# mc_ds.net
KiCad netlist of a schematic drawn in Altium Designer
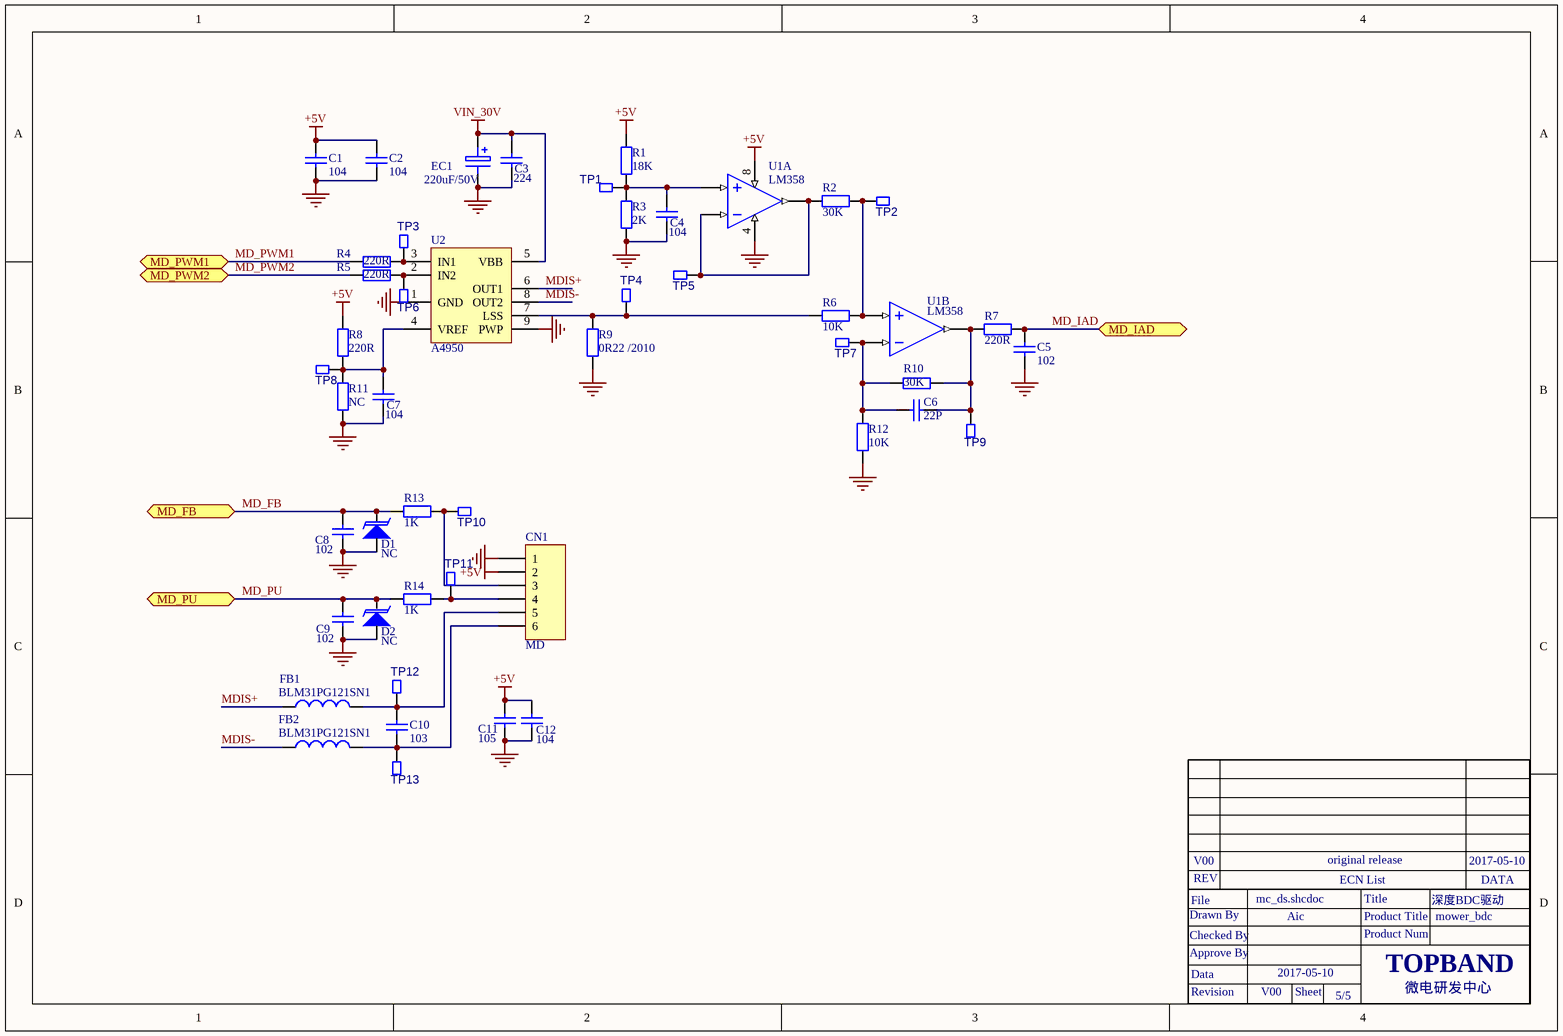
[diagram p0: mc_ds.SchDoc]

(export (version "E")
  (design (tool "Eeschema 10.0.6"))
  (components
    (comp (ref "C1")
      (value "104")
      (footprint "0603C")
      (libsource (lib "altium-import") (part "root_3_mirrored_Cap(0603)_"))
    )
    (comp (ref "C2")
      (value "104")
      (footprint "0603C")
      (libsource (lib "altium-import") (part "root_3_mirrored_Cap(0603)_"))
    )
    (comp (ref "C3")
      (value "224")
      (footprint "0805C")
      (libsource (lib "altium-import") (part "root_3_mirrored_Cap(0603)_"))
    )
    (comp (ref "C4")
      (value "104")
      (footprint "0603C")
      (libsource (lib "altium-import") (part "root_3_mirrored_Cap(0603)_"))
    )
    (comp (ref "C5")
      (value "102")
      (footprint "0603C")
      (libsource (lib "altium-import") (part "root_1_mirrored_Cap(0603)_"))
    )
    (comp (ref "C6")
      (value "22P")
      (footprint "0603C")
      (libsource (lib "altium-import") (part "root_0_mirrored_Cap(0603)_"))
    )
    (comp (ref "C7")
      (value "104")
      (footprint "0603C")
      (libsource (lib "altium-import") (part "root_3_mirrored_Cap(0603)_"))
    )
    (comp (ref "C8")
      (value "102")
      (footprint "0603C")
      (libsource (lib "altium-import") (part "root_1_mirrored_Cap(0603)_"))
    )
    (comp (ref "C9")
      (value "102")
      (footprint "0603C")
      (libsource (lib "altium-import") (part "root_1_mirrored_Cap(0603)_"))
    )
    (comp (ref "C10")
      (value "103")
      (footprint "0805C")
      (libsource (lib "altium-import") (part "root_1_mirrored_Cap(0603)_"))
    )
    (comp (ref "C11")
      (value "105")
      (footprint "0805C")
      (libsource (lib "altium-import") (part "root_1_mirrored_Cap(0603)_"))
    )
    (comp (ref "C12")
      (value "104")
      (footprint "0603C")
      (libsource (lib "altium-import") (part "root_1_mirrored_Cap(0603)_"))
    )
    (comp (ref "CN1")
      (value "MD")
      (footprint "CON6-2.54")
      (description "Header, 6-Pin")
      (fields (field (name "PUBLISHER") "Altium Limited"))
      (libsource (lib "Miscellaneous Connectors") (part "Header 6"))
    )
    (comp (ref "D1")
      (value "NC")
      (footprint "SOD-123")
      (description "TVS管")
      (fields (field (name "PART NUMBER") "Diode(TVS_贴片)_1"))
      (libsource (lib "分立器件1") (part "Diode(TVS_贴片)_1"))
    )
    (comp (ref "D2")
      (value "NC")
      (footprint "SOD-123")
      (description "TVS管")
      (fields (field (name "PART NUMBER") "Diode(TVS_贴片)_1"))
      (libsource (lib "分立器件1") (part "Diode(TVS_贴片)_1"))
    )
    (comp (ref "EC1")
      (value "220uF/50V")
      (footprint "EC10")
      (description "电解电容")
      (fields (field (name "PART NUMBER") "Electro(2.5mm)"))
      (libsource (lib "分立器件1") (part "Electro(2.5mm)"))
    )
    (comp (ref "FB1")
      (value "BLM31PG121SN1")
      (footprint "1206R")
      (description "电感")
      (fields (field (name "PART NUMBER") "Inductor"))
      (libsource (lib "分立器件1") (part "Inductor"))
    )
    (comp (ref "FB2")
      (value "BLM31PG121SN1")
      (footprint "1206R")
      (description "电感")
      (fields (field (name "PART NUMBER") "Inductor"))
      (libsource (lib "分立器件1") (part "Inductor"))
    )
    (comp (ref "R1")
      (value "18K")
      (footprint "0603R")
      (description "Resistor")
      (fields (field (name "PUBLISHER") "Altium Limited"))
      (libsource (lib "") (part "Res2_2"))
    )
    (comp (ref "R2")
      (value "30K")
      (footprint "0603R")
      (description "Resistor")
      (fields (field (name "PUBLISHER") "Altium Limited"))
      (libsource (lib "Miscellaneous Devices") (part "Res2"))
    )
    (comp (ref "R3")
      (value "2K")
      (footprint "0603R")
      (description "Resistor")
      (fields (field (name "PUBLISHER") "Altium Limited"))
      (libsource (lib "") (part "Res2_2"))
    )
    (comp (ref "R4")
      (value "220R")
      (footprint "0603R")
      (description "Resistor")
      (fields (field (name "PUBLISHER") "Altium Limited"))
      (libsource (lib "Miscellaneous Devices") (part "Res2"))
    )
    (comp (ref "R5")
      (value "220R")
      (footprint "0603R")
      (description "Resistor")
      (fields (field (name "PUBLISHER") "Altium Limited"))
      (libsource (lib "Miscellaneous Devices") (part "Res2"))
    )
    (comp (ref "R6")
      (value "10K")
      (footprint "0603R")
      (description "Resistor")
      (fields (field (name "PUBLISHER") "Altium Limited"))
      (libsource (lib "Miscellaneous Devices") (part "Res2"))
    )
    (comp (ref "R7")
      (value "220R")
      (footprint "0603R")
      (description "Resistor")
      (fields (field (name "PUBLISHER") "Altium Limited"))
      (libsource (lib "Miscellaneous Devices") (part "Res2"))
    )
    (comp (ref "R8")
      (value "220R")
      (footprint "0603R")
      (description "Resistor")
      (fields (field (name "PUBLISHER") "Altium Limited"))
      (libsource (lib "") (part "Res2_1"))
    )
    (comp (ref "R9")
      (value "0R22 /2010")
      (footprint "2010R")
      (description "Resistor")
      (fields (field (name "PUBLISHER") "Altium Limited"))
      (libsource (lib "") (part "Res2_1"))
    )
    (comp (ref "R10")
      (value "30K")
      (footprint "0603R")
      (description "Resistor")
      (fields (field (name "PUBLISHER") "Altium Limited"))
      (libsource (lib "") (part "Res2_3"))
    )
    (comp (ref "R11")
      (value "NC")
      (footprint "0603R")
      (description "Resistor")
      (fields (field (name "PUBLISHER") "Altium Limited"))
      (libsource (lib "") (part "Res2_2"))
    )
    (comp (ref "R12")
      (value "10K")
      (footprint "0603R")
      (description "Resistor")
      (fields (field (name "PUBLISHER") "Altium Limited"))
      (libsource (lib "") (part "Res2_2"))
    )
    (comp (ref "R13")
      (value "1K")
      (footprint "0603R")
      (description "Resistor")
      (fields (field (name "PUBLISHER") "Altium Limited"))
      (libsource (lib "") (part "Res2_3"))
    )
    (comp (ref "R14")
      (value "1K")
      (footprint "0603R")
      (description "Resistor")
      (fields (field (name "PUBLISHER") "Altium Limited"))
      (libsource (lib "") (part "Res2_3"))
    )
    (comp (ref "TP1") (value "TP") (footprint "TEST-0.8MM") (libsource (lib "Topband1") (part "TP")))
    (comp (ref "TP2") (value "TP") (footprint "TEST-0.8MM") (libsource (lib "Topband1") (part "TP")))
    (comp (ref "TP3") (value "TP") (footprint "TEST-0.8MM") (libsource (lib "Topband1") (part "TP")))
    (comp (ref "TP4") (value "TP") (footprint "TEST-0.8MM") (libsource (lib "Topband1") (part "TP")))
    (comp (ref "TP5") (value "TP") (footprint "TEST-0.8MM") (libsource (lib "Topband1") (part "TP")))
    (comp (ref "TP6") (value "TP") (footprint "TEST-0.8MM") (libsource (lib "Topband1") (part "TP")))
    (comp (ref "TP7") (value "TP") (footprint "TEST-0.8MM") (libsource (lib "Topband1") (part "TP")))
    (comp (ref "TP8") (value "TP") (footprint "TEST-0.8MM") (libsource (lib "Topband1") (part "TP")))
    (comp (ref "TP9") (value "TP") (footprint "TEST-0.8MM") (libsource (lib "Topband1") (part "TP")))
    (comp (ref "TP10") (value "TP") (footprint "TEST-0.8MM") (libsource (lib "Topband1") (part "TP")))
    (comp (ref "TP11") (value "TP") (footprint "TEST-0.8MM") (libsource (lib "Topband1") (part "TP")))
    (comp (ref "TP12") (value "TP") (footprint "TEST-0.8MM") (libsource (lib "Topband1") (part "TP")))
    (comp (ref "TP13") (value "TP") (footprint "TEST-0.8MM") (libsource (lib "Topband1") (part "TP")))
    (comp (ref "U1")
      (value "LM358")
      (footprint "SO-8")
      (description "集成电路")
      (fields (field (name "PART NUMBER") "IC_LM358"))
      (libsource (lib "接插器件+IC") (part "IC_LM358"))
    )
    (comp (ref "U2") (value "A4950") (footprint "SO-8 - E") (libsource (lib "Schlib") (part "A4950")))
  )
  (nets
    (net (code "1") (name "+5V") (class "Default")
      (node (ref "C1") (pin "2") (pinfunction "2_2") (pintype "passive"))
      (node (ref "C11") (pin "1") (pinfunction "1_1") (pintype "passive"))
      (node (ref "C12") (pin "1") (pinfunction "1_1") (pintype "passive"))
      (node (ref "C2") (pin "2") (pinfunction "2_2") (pintype "passive"))
      (node (ref "CN1") (pin "2") (pinfunction "2_2") (pintype "passive"))
      (node (ref "R1") (pin "2") (pinfunction "2_2") (pintype "passive"))
      (node (ref "R8") (pin "1") (pinfunction "1_1") (pintype "passive"))
      (node (ref "U1") (pin "8") (pinfunction "VCC_8") (pintype "input"))
    )
    (net (code "2") (name "/MDIS+") (class "Default")
      (node (ref "FB1") (pin "1") (pinfunction "1_1") (pintype "passive"))
      (node (ref "U2") (pin "6") (pinfunction "OUT1_6") (pintype "passive"))
    )
    (net (code "3") (name "/MDIS-") (class "Default")
      (node (ref "FB2") (pin "1") (pinfunction "1_1") (pintype "passive"))
      (node (ref "U2") (pin "8") (pinfunction "OUT2_8") (pintype "passive"))
    )
    (net (code "4") (name "/MD_FB") (class "Default")
      (node (ref "C8") (pin "1") (pinfunction "1_1") (pintype "passive"))
      (node (ref "D1") (pin "K") (pinfunction "K_K") (pintype "passive"))
      (node (ref "R13") (pin "2") (pinfunction "2_2") (pintype "passive"))
    )
    (net (code "5") (name "/MD_IAD") (class "Default")
      (node (ref "C5") (pin "1") (pinfunction "1_1") (pintype "passive"))
      (node (ref "R7") (pin "2") (pinfunction "2_2") (pintype "passive"))
    )
    (net (code "6") (name "/MD_PU") (class "Default")
      (node (ref "C9") (pin "1") (pinfunction "1_1") (pintype "passive"))
      (node (ref "D2") (pin "K") (pinfunction "K_K") (pintype "passive"))
      (node (ref "R14") (pin "2") (pinfunction "2_2") (pintype "passive"))
    )
    (net (code "7") (name "/MD_PWM1") (class "Default")
      (node (ref "R4") (pin "1") (pinfunction "1_1") (pintype "passive"))
    )
    (net (code "8") (name "/MD_PWM2") (class "Default")
      (node (ref "R5") (pin "1") (pinfunction "1_1") (pintype "passive"))
    )
    (net (code "9") (name "GND") (class "Default")
      (node (ref "C1") (pin "1") (pinfunction "1_1") (pintype "passive"))
      (node (ref "C11") (pin "2") (pinfunction "2_2") (pintype "passive"))
      (node (ref "C12") (pin "2") (pinfunction "2_2") (pintype "passive"))
      (node (ref "C2") (pin "1") (pinfunction "1_1") (pintype "passive"))
      (node (ref "C3") (pin "1") (pinfunction "1_1") (pintype "passive"))
      (node (ref "C4") (pin "1") (pinfunction "1_1") (pintype "passive"))
      (node (ref "C5") (pin "2") (pinfunction "2_2") (pintype "passive"))
      (node (ref "C7") (pin "1") (pinfunction "1_1") (pintype "passive"))
      (node (ref "C8") (pin "2") (pinfunction "2_2") (pintype "passive"))
      (node (ref "C9") (pin "2") (pinfunction "2_2") (pintype "passive"))
      (node (ref "CN1") (pin "1") (pinfunction "1_1") (pintype "passive"))
      (node (ref "D1") (pin "A") (pinfunction "A_A") (pintype "passive"))
      (node (ref "D2") (pin "A") (pinfunction "A_A") (pintype "passive"))
      (node (ref "EC1") (pin "2") (pinfunction "2_2") (pintype "passive"))
      (node (ref "R11") (pin "1") (pinfunction "1_1") (pintype "passive"))
      (node (ref "R12") (pin "1") (pinfunction "1_1") (pintype "passive"))
      (node (ref "R3") (pin "1") (pinfunction "1_1") (pintype "passive"))
      (node (ref "R9") (pin "2") (pinfunction "2_2") (pintype "passive"))
      (node (ref "U1") (pin "4") (pinfunction "GND_4") (pintype "input"))
      (node (ref "U2") (pin "1") (pinfunction "GND_1") (pintype "passive"))
      (node (ref "U2") (pin "9") (pinfunction "PWP_9") (pintype "passive"))
    )
    (net (code "10") (name "Net-(C10-Pad1)") (class "Default")
      (node (ref "C10") (pin "1") (pinfunction "1_1") (pintype "passive"))
      (node (ref "CN1") (pin "5") (pinfunction "5_5") (pintype "passive"))
      (node (ref "FB1") (pin "2") (pinfunction "2_2") (pintype "passive"))
      (node (ref "TP12") (pin "1") (pintype "passive"))
    )
    (net (code "11") (name "Net-(C10-Pad2)") (class "Default")
      (node (ref "C10") (pin "2") (pinfunction "2_2") (pintype "passive"))
      (node (ref "CN1") (pin "6") (pinfunction "6_6") (pintype "passive"))
      (node (ref "FB2") (pin "2") (pinfunction "2_2") (pintype "passive"))
      (node (ref "TP13") (pin "1") (pintype "passive"))
    )
    (net (code "12") (name "Net-(CN1-Pad3)") (class "Default")
      (node (ref "CN1") (pin "3") (pinfunction "3_3") (pintype "passive"))
      (node (ref "R13") (pin "1") (pinfunction "1_1") (pintype "passive"))
      (node (ref "TP10") (pin "1") (pintype "passive"))
    )
    (net (code "13") (name "Net-(CN1-Pad4)") (class "Default")
      (node (ref "CN1") (pin "4") (pinfunction "4_4") (pintype "passive"))
      (node (ref "R14") (pin "1") (pinfunction "1_1") (pintype "passive"))
      (node (ref "TP11") (pin "1") (pintype "passive"))
    )
    (net (code "14") (name "Net-(U1A-+IN1)") (class "Default")
      (node (ref "C4") (pin "2") (pinfunction "2_2") (pintype "passive"))
      (node (ref "R1") (pin "1") (pinfunction "1_1") (pintype "passive"))
      (node (ref "R3") (pin "2") (pinfunction "2_2") (pintype "passive"))
      (node (ref "TP1") (pin "1") (pintype "passive"))
      (node (ref "U1") (pin "5") (pinfunction "+IN1_5") (pintype "input"))
    )
    (net (code "15") (name "Net-(U1A--IN1)") (class "Default")
      (node (ref "R2") (pin "1") (pinfunction "1_1") (pintype "passive"))
      (node (ref "TP5") (pin "1") (pintype "passive"))
      (node (ref "U1") (pin "6") (pinfunction "-IN1_6") (pintype "input"))
      (node (ref "U1") (pin "7") (pinfunction "OUT1_7") (pintype "output"))
    )
    (net (code "16") (name "Net-(U1B--IN2)") (class "Default")
      (node (ref "C6") (pin "2") (pinfunction "2_2") (pintype "passive"))
      (node (ref "R10") (pin "2") (pinfunction "2_2") (pintype "passive"))
      (node (ref "R12") (pin "2") (pinfunction "2_2") (pintype "passive"))
      (node (ref "TP7") (pin "1") (pintype "passive"))
      (node (ref "U1") (pin "2") (pinfunction "-IN2_2") (pintype "input"))
    )
    (net (code "17") (name "Net-(U1B-IN2+)") (class "Default")
      (node (ref "R2") (pin "2") (pinfunction "2_2") (pintype "passive"))
      (node (ref "R6") (pin "2") (pinfunction "2_2") (pintype "passive"))
      (node (ref "TP2") (pin "1") (pintype "passive"))
      (node (ref "U1") (pin "3") (pinfunction "IN2+_3") (pintype "input"))
    )
    (net (code "18") (name "Net-(U1B-OUT2)") (class "Default")
      (node (ref "C6") (pin "1") (pinfunction "1_1") (pintype "passive"))
      (node (ref "R10") (pin "1") (pinfunction "1_1") (pintype "passive"))
      (node (ref "R7") (pin "1") (pinfunction "1_1") (pintype "passive"))
      (node (ref "TP9") (pin "1") (pintype "passive"))
      (node (ref "U1") (pin "1") (pinfunction "OUT2_1") (pintype "output"))
    )
    (net (code "19") (name "Net-(U2-IN1)") (class "Default")
      (node (ref "R4") (pin "2") (pinfunction "2_2") (pintype "passive"))
      (node (ref "TP3") (pin "1") (pintype "passive"))
      (node (ref "U2") (pin "3") (pinfunction "IN1_3") (pintype "passive"))
    )
    (net (code "20") (name "Net-(U2-IN2)") (class "Default")
      (node (ref "R5") (pin "2") (pinfunction "2_2") (pintype "passive"))
      (node (ref "TP6") (pin "1") (pintype "passive"))
      (node (ref "U2") (pin "2") (pinfunction "IN2_2") (pintype "passive"))
    )
    (net (code "21") (name "Net-(U2-LSS)") (class "Default")
      (node (ref "R6") (pin "1") (pinfunction "1_1") (pintype "passive"))
      (node (ref "R9") (pin "1") (pinfunction "1_1") (pintype "passive"))
      (node (ref "TP4") (pin "1") (pintype "passive"))
      (node (ref "U2") (pin "7") (pinfunction "LSS_7") (pintype "passive"))
    )
    (net (code "22") (name "Net-(U2-VREF)") (class "Default")
      (node (ref "C7") (pin "2") (pinfunction "2_2") (pintype "passive"))
      (node (ref "R11") (pin "2") (pinfunction "2_2") (pintype "passive"))
      (node (ref "R8") (pin "2") (pinfunction "2_2") (pintype "passive"))
      (node (ref "TP8") (pin "1") (pintype "passive"))
      (node (ref "U2") (pin "4") (pinfunction "VREF_4") (pintype "passive"))
    )
    (net (code "23") (name "VIN_30V") (class "Default")
      (node (ref "C3") (pin "2") (pinfunction "2_2") (pintype "passive"))
      (node (ref "EC1") (pin "1") (pinfunction "1_1") (pintype "passive"))
      (node (ref "U2") (pin "5") (pinfunction "VBB_5") (pintype "passive"))
    )
  )
)
